# Sheet1.net
KiCad netlist of a schematic drawn in Altium Designer
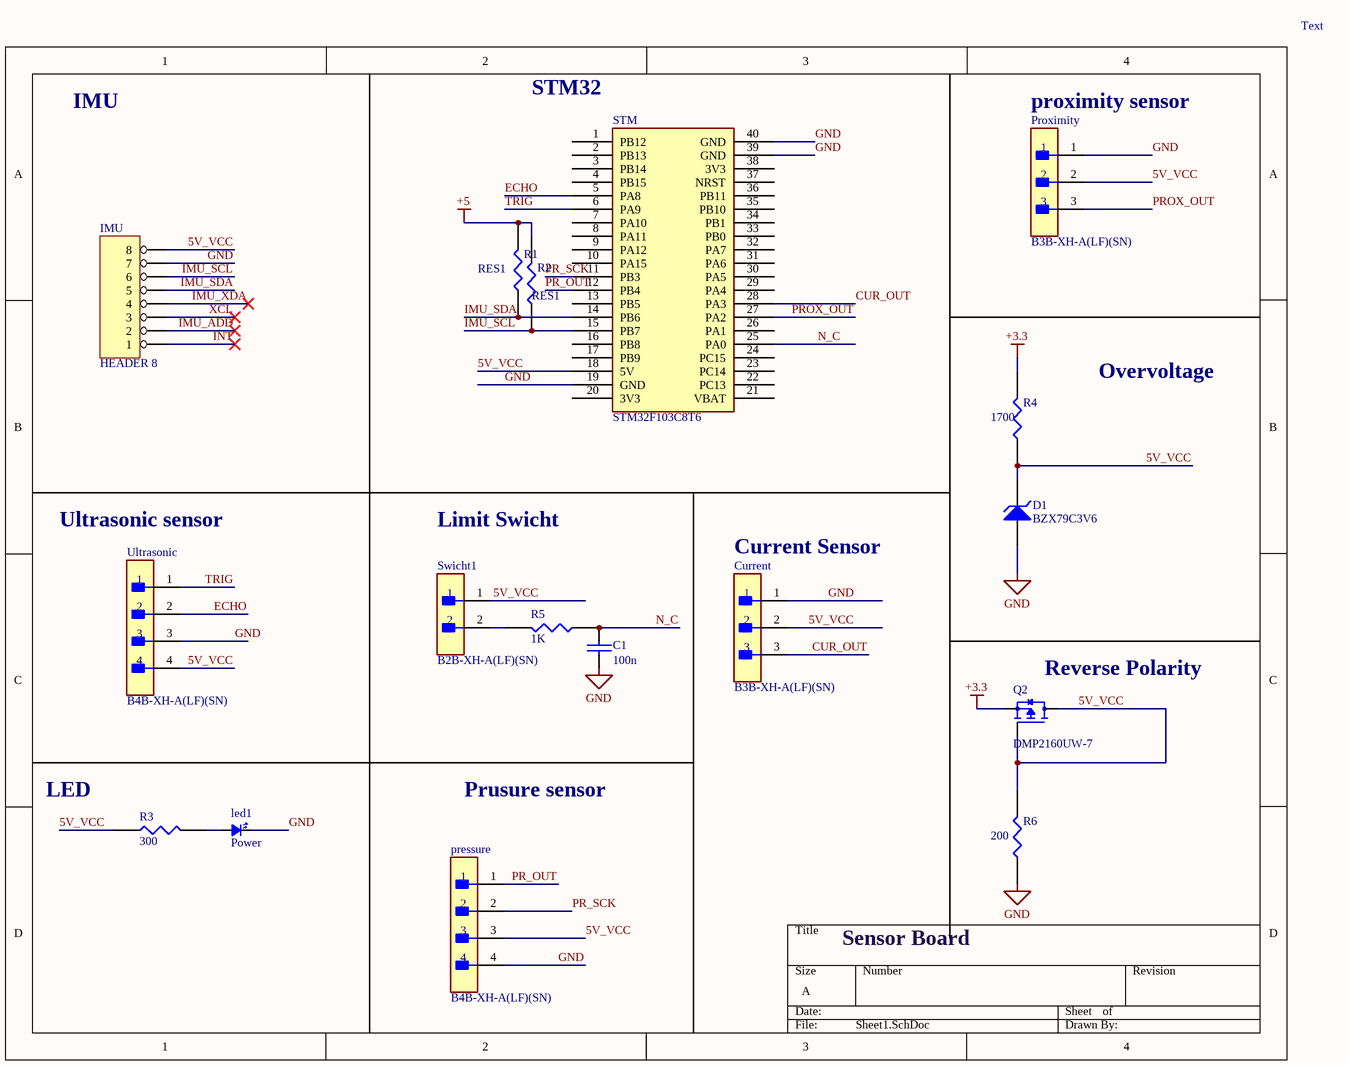
[diagram p0: Sheet1.SchDoc]

(export (version "E")
  (design (tool "Eeschema 10.0.6"))
  (components
    (comp (ref "C1")
      (value "100n")
      (footprint "RAD0.1")
      (description "Capacitor")
      (libsource (lib "ALEX TRAINING CENTER1") (part "CAP"))
    )
    (comp (ref "Current")
      (value "B3B-XH-A(LF)(SN)")
      (footprint "FP-B3B-XH-A_LF_SN-MFG")
      (description "CONN HEADER VERT 3POS 2.5MM")
      (libsource (lib "Altium Content Vault") (part "0d3f023dd272f625e17a2be33dea85f"))
    )
    (comp (ref "D1")
      (value "BZX79C3V6")
      (footprint "FAIR-DO-35-2")
      (description "Zener Diode, 3.6 V, 5 mA, -65 to 200 degC, 2-Pin DO-35, RoHS, Bulk")
      (fields (field (name "MANUFACTURER") "Fairchild Semiconductor") (field (name "TOLERANCE") "6%"))
      (libsource (lib "Mohamed Elhofy") (part "DZEN-AK-2"))
    )
    (comp (ref "IMU")
      (value "HEADER 8")
      (footprint "SIP8")
      (description "8 Pin Header")
      (libsource (lib "ALEX TRAINING CENTER1") (part "HEADER 8"))
    )
    (comp (ref "led1")
      (value "Power")
      (footprint "LED-05 R")
      (libsource (lib "ALEX TRAINING CENTER1") (part "LED_1"))
    )
    (comp (ref "pressure")
      (value "B4B-XH-A(LF)(SN)")
      (footprint "FP-B4B-XH-A_LF_SN-MFG")
      (description "CONN HEADER VERT 4POS 2.5MM")
      (libsource (lib "Altium Content Vault") (part "299a8cea1bdcbc3624fe62c390fa72c"))
    )
    (comp (ref "Proximity")
      (value "B3B-XH-A(LF)(SN)")
      (footprint "FP-B3B-XH-A_LF_SN-MFG")
      (description "CONN HEADER VERT 3POS 2.5MM")
      (libsource (lib "Altium Content Vault") (part "0d3f023dd272f625e17a2be33dea85f"))
    )
    (comp (ref "Q2")
      (value "DMP2160UW-7")
      (footprint "TRANS_DMP2160UW-7")
      (description "P-Channel 20 V 1.5A (Ta) 350mW (Ta) Surface Mount SOT-323")
      (fields (field (name "MF") "Diodes Inc."))
      (libsource (lib "ALEX TRAINING CENTER1") (part "DMP2160UW-7"))
    )
    (comp (ref "R1")
      (value "RES1")
      (footprint "AXIAL0.3")
      (libsource (lib "ALEX TRAINING CENTER1") (part "RES1"))
    )
    (comp (ref "R2")
      (value "RES1")
      (footprint "AXIAL0.3")
      (libsource (lib "ALEX TRAINING CENTER1") (part "RES1"))
    )
    (comp (ref "R3")
      (value "300")
      (footprint "AXIAL0.3")
      (libsource (lib "ALEX TRAINING CENTER1") (part "RES1"))
    )
    (comp (ref "R4")
      (value "1700")
      (footprint "AXIAL0.3")
      (libsource (lib "ALEX TRAINING CENTER1") (part "RES1"))
    )
    (comp (ref "R5")
      (value "1K")
      (footprint "AXIAL0.3")
      (libsource (lib "ALEX TRAINING CENTER1") (part "RES1"))
    )
    (comp (ref "R6")
      (value "200")
      (footprint "AXIAL0.3")
      (libsource (lib "ALEX TRAINING CENTER1") (part "RES1"))
    )
    (comp (ref "STM")
      (value "STM32F103C8T6")
      (footprint "Stm32 BluePill")
      (description "Designed By @Alixahedi")
      (libsource (lib "Schlib2") (part "BluePill"))
    )
    (comp (ref "Swicht1")
      (value "B2B-XH-A(LF)(SN)")
      (footprint "FP-B2B-XH-A_LF_SN-MFG")
      (description "CONN HEADER VERT 2POS 2.5MM")
      (libsource (lib "Altium Content Vault") (part "3bc925449376181038e59eaffc5286c"))
    )
    (comp (ref "Ultrasonic")
      (value "B4B-XH-A(LF)(SN)")
      (footprint "FP-B4B-XH-A_LF_SN-MFG")
      (description "CONN HEADER VERT 4POS 2.5MM")
      (libsource (lib "Altium Content Vault") (part "299a8cea1bdcbc3624fe62c390fa72c"))
    )
  )
  (nets
    (net (code "1") (name "+3.3") (class "Default")
      (node (ref "Q2") (pin "2") (pinfunction "S_2") (pintype "passive"))
      (node (ref "R4") (pin "2") (pinfunction "2_2") (pintype "passive"))
    )
    (net (code "2") (name "+5") (class "Default")
      (node (ref "R1") (pin "2") (pinfunction "2_2") (pintype "passive"))
      (node (ref "R2") (pin "2") (pinfunction "2_2") (pintype "passive"))
    )
    (net (code "3") (name "/5V_VCC") (class "Default")
      (node (ref "Current") (pin "2") (pinfunction "2_2") (pintype "passive"))
      (node (ref "D1") (pin "2") (pinfunction "K_2") (pintype "passive"))
      (node (ref "IMU") (pin "8") (pinfunction "8_8") (pintype "passive"))
      (node (ref "Proximity") (pin "2") (pinfunction "2_2") (pintype "passive"))
      (node (ref "Q2") (pin "1") (pinfunction "G_1") (pintype "passive"))
      (node (ref "Q2") (pin "3") (pinfunction "D_3") (pintype "passive"))
      (node (ref "R3") (pin "1") (pinfunction "1_1") (pintype "passive"))
      (node (ref "R4") (pin "1") (pinfunction "1_1") (pintype "passive"))
      (node (ref "R6") (pin "2") (pinfunction "2_2") (pintype "passive"))
      (node (ref "STM") (pin "18") (pinfunction "5V_18") (pintype "passive"))
      (node (ref "Swicht1") (pin "1") (pinfunction "1_1") (pintype "passive"))
      (node (ref "Ultrasonic") (pin "4") (pinfunction "4_4") (pintype "passive"))
      (node (ref "pressure") (pin "3") (pinfunction "3_3") (pintype "passive"))
    )
    (net (code "4") (name "/CUR_OUT") (class "Default")
      (node (ref "Current") (pin "3") (pinfunction "3_3") (pintype "passive"))
      (node (ref "STM") (pin "28") (pinfunction "PA3_28") (pintype "passive"))
    )
    (net (code "5") (name "/ECHO") (class "Default")
      (node (ref "STM") (pin "5") (pinfunction "PA8_5") (pintype "passive"))
      (node (ref "Ultrasonic") (pin "2") (pinfunction "2_2") (pintype "passive"))
    )
    (net (code "6") (name "/IMU_ADD") (class "Default")
      (node (ref "IMU") (pin "2") (pinfunction "2_2") (pintype "passive+no_connect"))
    )
    (net (code "7") (name "/IMU_SCL") (class "Default")
      (node (ref "IMU") (pin "6") (pinfunction "6_6") (pintype "passive"))
      (node (ref "R2") (pin "1") (pinfunction "1_1") (pintype "passive"))
      (node (ref "STM") (pin "15") (pinfunction "PB7_15") (pintype "passive"))
    )
    (net (code "8") (name "/IMU_SDA") (class "Default")
      (node (ref "IMU") (pin "5") (pinfunction "5_5") (pintype "passive"))
      (node (ref "R1") (pin "1") (pinfunction "1_1") (pintype "passive"))
      (node (ref "STM") (pin "14") (pinfunction "PB6_14") (pintype "passive"))
    )
    (net (code "9") (name "/IMU_XDA") (class "Default")
      (node (ref "IMU") (pin "4") (pinfunction "4_4") (pintype "passive+no_connect"))
    )
    (net (code "10") (name "/INT") (class "Default")
      (node (ref "IMU") (pin "1") (pinfunction "1_1") (pintype "passive+no_connect"))
    )
    (net (code "11") (name "/N_C") (class "Default")
      (node (ref "C1") (pin "1") (pinfunction "1_1") (pintype "passive"))
      (node (ref "R5") (pin "1") (pinfunction "1_1") (pintype "passive"))
      (node (ref "STM") (pin "25") (pinfunction "PA0_25") (pintype "passive"))
    )
    (net (code "12") (name "/PROX_OUT") (class "Default")
      (node (ref "Proximity") (pin "3") (pinfunction "3_3") (pintype "passive"))
      (node (ref "STM") (pin "27") (pinfunction "PA2_27") (pintype "passive"))
    )
    (net (code "13") (name "/PR_OUT") (class "Default")
      (node (ref "STM") (pin "12") (pinfunction "PB4_12") (pintype "passive"))
      (node (ref "pressure") (pin "1") (pinfunction "1_1") (pintype "passive"))
    )
    (net (code "14") (name "/PR_SCK") (class "Default")
      (node (ref "STM") (pin "11") (pinfunction "PB3_11") (pintype "passive"))
      (node (ref "pressure") (pin "2") (pinfunction "2_2") (pintype "passive"))
    )
    (net (code "15") (name "/TRIG") (class "Default")
      (node (ref "STM") (pin "6") (pinfunction "PA9_6") (pintype "passive"))
      (node (ref "Ultrasonic") (pin "1") (pinfunction "1_1") (pintype "passive"))
    )
    (net (code "16") (name "/XCL") (class "Default")
      (node (ref "IMU") (pin "3") (pinfunction "3_3") (pintype "passive+no_connect"))
    )
    (net (code "17") (name "GND") (class "Default")
      (node (ref "C1") (pin "2") (pinfunction "2_2") (pintype "passive"))
      (node (ref "Current") (pin "1") (pinfunction "1_1") (pintype "passive"))
      (node (ref "D1") (pin "1") (pinfunction "A_1") (pintype "passive"))
      (node (ref "IMU") (pin "7") (pinfunction "7_7") (pintype "passive"))
      (node (ref "Proximity") (pin "1") (pinfunction "1_1") (pintype "passive"))
      (node (ref "R6") (pin "1") (pinfunction "1_1") (pintype "passive"))
      (node (ref "STM") (pin "19") (pinfunction "GND_19") (pintype "passive"))
      (node (ref "STM") (pin "39") (pinfunction "GND_39") (pintype "passive"))
      (node (ref "STM") (pin "40") (pinfunction "GND_40") (pintype "passive"))
      (node (ref "Ultrasonic") (pin "3") (pinfunction "3_3") (pintype "passive"))
      (node (ref "led1") (pin "2") (pinfunction "2_2") (pintype "passive"))
      (node (ref "pressure") (pin "4") (pinfunction "4_4") (pintype "passive"))
    )
    (net (code "18") (name "Net-(R3-Pad2)") (class "Default")
      (node (ref "R3") (pin "2") (pinfunction "2_2") (pintype "passive"))
      (node (ref "led1") (pin "1") (pinfunction "1_1") (pintype "passive"))
    )
    (net (code "19") (name "Net-(R5-Pad2)") (class "Default")
      (node (ref "R5") (pin "2") (pinfunction "2_2") (pintype "passive"))
      (node (ref "Swicht1") (pin "2") (pinfunction "2_2") (pintype "passive"))
    )
    (net (code "20") (name "unconnected-(STM-3V3-Pad20)") (class "Default")
      (node (ref "STM") (pin "20") (pinfunction "3V3_20") (pintype "passive"))
    )
    (net (code "21") (name "unconnected-(STM-3V3-Pad38)") (class "Default")
      (node (ref "STM") (pin "38") (pinfunction "3V3_38") (pintype "passive"))
    )
    (net (code "22") (name "unconnected-(STM-NRST-Pad37)") (class "Default")
      (node (ref "STM") (pin "37") (pinfunction "NRST_37") (pintype "passive"))
    )
    (net (code "23") (name "unconnected-(STM-PA1-Pad26)") (class "Default")
      (node (ref "STM") (pin "26") (pinfunction "PA1_26") (pintype "passive"))
    )
    (net (code "24") (name "unconnected-(STM-PA4-Pad29)") (class "Default")
      (node (ref "STM") (pin "29") (pinfunction "PA4_29") (pintype "passive"))
    )
    (net (code "25") (name "unconnected-(STM-PA5-Pad30)") (class "Default")
      (node (ref "STM") (pin "30") (pinfunction "PA5_30") (pintype "passive"))
    )
    (net (code "26") (name "unconnected-(STM-PA6-Pad31)") (class "Default")
      (node (ref "STM") (pin "31") (pinfunction "PA6_31") (pintype "passive"))
    )
    (net (code "27") (name "unconnected-(STM-PA7-Pad32)") (class "Default")
      (node (ref "STM") (pin "32") (pinfunction "PA7_32") (pintype "passive"))
    )
    (net (code "28") (name "unconnected-(STM-PA10-Pad7)") (class "Default")
      (node (ref "STM") (pin "7") (pinfunction "PA10_7") (pintype "passive"))
    )
    (net (code "29") (name "unconnected-(STM-PA11-Pad8)") (class "Default")
      (node (ref "STM") (pin "8") (pinfunction "PA11_8") (pintype "passive"))
    )
    (net (code "30") (name "unconnected-(STM-PA12-Pad9)") (class "Default")
      (node (ref "STM") (pin "9") (pinfunction "PA12_9") (pintype "passive"))
    )
    (net (code "31") (name "unconnected-(STM-PA15-Pad10)") (class "Default")
      (node (ref "STM") (pin "10") (pinfunction "PA15_10") (pintype "passive"))
    )
    (net (code "32") (name "unconnected-(STM-PB0-Pad33)") (class "Default")
      (node (ref "STM") (pin "33") (pinfunction "PB0_33") (pintype "passive"))
    )
    (net (code "33") (name "unconnected-(STM-PB1-Pad34)") (class "Default")
      (node (ref "STM") (pin "34") (pinfunction "PB1_34") (pintype "passive"))
    )
    (net (code "34") (name "unconnected-(STM-PB5-Pad13)") (class "Default")
      (node (ref "STM") (pin "13") (pinfunction "PB5_13") (pintype "passive"))
    )
    (net (code "35") (name "unconnected-(STM-PB8-Pad16)") (class "Default")
      (node (ref "STM") (pin "16") (pinfunction "PB8_16") (pintype "passive"))
    )
    (net (code "36") (name "unconnected-(STM-PB9-Pad17)") (class "Default")
      (node (ref "STM") (pin "17") (pinfunction "PB9_17") (pintype "passive"))
    )
    (net (code "37") (name "unconnected-(STM-PB10-Pad35)") (class "Default")
      (node (ref "STM") (pin "35") (pinfunction "PB10_35") (pintype "passive"))
    )
    (net (code "38") (name "unconnected-(STM-PB11-Pad36)") (class "Default")
      (node (ref "STM") (pin "36") (pinfunction "PB11_36") (pintype "passive"))
    )
    (net (code "39") (name "unconnected-(STM-PB12-Pad1)") (class "Default")
      (node (ref "STM") (pin "1") (pinfunction "PB12_1") (pintype "passive"))
    )
    (net (code "40") (name "unconnected-(STM-PB13-Pad2)") (class "Default")
      (node (ref "STM") (pin "2") (pinfunction "PB13_2") (pintype "passive"))
    )
    (net (code "41") (name "unconnected-(STM-PB14-Pad3)") (class "Default")
      (node (ref "STM") (pin "3") (pinfunction "PB14_3") (pintype "passive"))
    )
    (net (code "42") (name "unconnected-(STM-PB15-Pad4)") (class "Default")
      (node (ref "STM") (pin "4") (pinfunction "PB15_4") (pintype "passive"))
    )
    (net (code "43") (name "unconnected-(STM-PC13-Pad22)") (class "Default")
      (node (ref "STM") (pin "22") (pinfunction "PC13_22") (pintype "passive"))
    )
    (net (code "44") (name "unconnected-(STM-PC14-Pad23)") (class "Default")
      (node (ref "STM") (pin "23") (pinfunction "PC14_23") (pintype "passive"))
    )
    (net (code "45") (name "unconnected-(STM-PC15-Pad24)") (class "Default")
      (node (ref "STM") (pin "24") (pinfunction "PC15_24") (pintype "passive"))
    )
    (net (code "46") (name "unconnected-(STM-VBAT-Pad21)") (class "Default")
      (node (ref "STM") (pin "21") (pinfunction "VBAT_21") (pintype "passive"))
    )
  )
)
